# Controllerboard.net
KiCad netlist of a schematic drawn in EAGLE
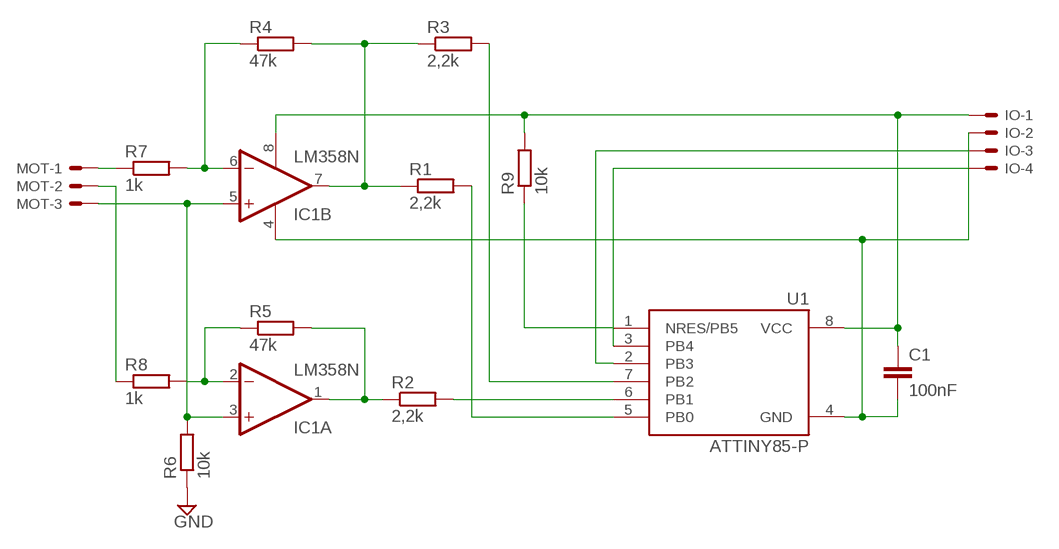
[diagram p0: schematic, sheet 1]

(export (version "E")
  (design (tool "Eeschema 10.0.6"))
  (components
    (comp (ref "C1")
      (value "100nF")
      (footprint "eagle-import:C025-024X044")
      (libsource (lib "eagle-import") (part "C-EU025-024X044"))
    )
    (comp (ref "IC1")
      (value "LM358N")
      (footprint "eagle-import:DIL08")
      (libsource (lib "eagle-import") (part "LM358N"))
    )
    (comp (ref "IO")
      (value "KK-156-4")
      (footprint "eagle-import:KK-156-4")
      (libsource (lib "eagle-import") (part "KK-156-4"))
    )
    (comp (ref "MOT")
      (value "KK-156-3")
      (footprint "eagle-import:KK-156-3")
      (libsource (lib "eagle-import") (part "KK-156-3"))
    )
    (comp (ref "R1")
      (value "2,2k")
      (footprint "eagle-import:0204_7")
      (libsource (lib "eagle-import") (part "resistor_R-EU_0204/7"))
    )
    (comp (ref "R2")
      (value "2,2k")
      (footprint "eagle-import:0204_7")
      (libsource (lib "eagle-import") (part "resistor_R-EU_0204/7"))
    )
    (comp (ref "R3")
      (value "2,2k")
      (footprint "eagle-import:0204_7")
      (libsource (lib "eagle-import") (part "resistor_R-EU_0204/7"))
    )
    (comp (ref "R4")
      (value "47k")
      (footprint "eagle-import:0204_7")
      (libsource (lib "eagle-import") (part "resistor_R-EU_0204/7"))
    )
    (comp (ref "R5")
      (value "47k")
      (footprint "eagle-import:0204_7")
      (libsource (lib "eagle-import") (part "resistor_R-EU_0204/7"))
    )
    (comp (ref "R6")
      (value "10k")
      (footprint "eagle-import:0204_7")
      (libsource (lib "eagle-import") (part "resistor_R-EU_0204/7"))
    )
    (comp (ref "R7")
      (value "1k")
      (footprint "eagle-import:0204_7")
      (libsource (lib "eagle-import") (part "resistor_R-EU_0204/7"))
    )
    (comp (ref "R8")
      (value "1k")
      (footprint "eagle-import:0204_7")
      (libsource (lib "eagle-import") (part "resistor_R-EU_0204/7"))
    )
    (comp (ref "R9")
      (value "10k")
      (footprint "eagle-import:0204_7")
      (libsource (lib "eagle-import") (part "R-EU_0204/7"))
    )
    (comp (ref "U1")
      (value "ATTINY85-P")
      (footprint "eagle-import:PDIP08_300MIL")
      (libsource (lib "eagle-import") (part "ATTINY85P-"))
    )
  )
  (nets
    (net (code "1") (name "GND") (class "Default")
      (node (ref "C1") (pin "2") (pinfunction "2_2") (pintype "passive"))
      (node (ref "IC1") (pin "4") (pinfunction "V-_4") (pintype "power_in"))
      (node (ref "IO") (pin "2") (pinfunction "S_2") (pintype "passive"))
      (node (ref "R6") (pin "1") (pinfunction "1_1") (pintype "passive"))
      (node (ref "U1") (pin "4") (pinfunction "GND_4") (pintype "power_in"))
    )
    (net (code "2") (name "Net-(IC1A-+IN)") (class "Default")
      (node (ref "IC1") (pin "3") (pinfunction "+IN_3") (pintype "input"))
      (node (ref "IC1") (pin "5") (pinfunction "+IN_5") (pintype "input"))
      (node (ref "MOT") (pin "3") (pinfunction "S_3") (pintype "passive"))
      (node (ref "R6") (pin "2") (pinfunction "2_2") (pintype "passive"))
    )
    (net (code "3") (name "Net-(IC1A--IN)") (class "Default")
      (node (ref "IC1") (pin "2") (pinfunction "-IN_2") (pintype "input"))
      (node (ref "R5") (pin "1") (pinfunction "1_1") (pintype "passive"))
      (node (ref "R8") (pin "2") (pinfunction "2_2") (pintype "passive"))
    )
    (net (code "4") (name "Net-(IC1A-OUT)") (class "Default")
      (node (ref "IC1") (pin "1") (pinfunction "OUT_1") (pintype "output"))
      (node (ref "R2") (pin "1") (pinfunction "1_1") (pintype "passive"))
      (node (ref "R5") (pin "2") (pinfunction "2_2") (pintype "passive"))
    )
    (net (code "5") (name "Net-(IC1B--IN)") (class "Default")
      (node (ref "IC1") (pin "6") (pinfunction "-IN_6") (pintype "input"))
      (node (ref "R4") (pin "1") (pinfunction "1_1") (pintype "passive"))
      (node (ref "R7") (pin "2") (pinfunction "2_2") (pintype "passive"))
    )
    (net (code "6") (name "Net-(IC1B-OUT)") (class "Default")
      (node (ref "IC1") (pin "7") (pinfunction "OUT_7") (pintype "output"))
      (node (ref "R1") (pin "1") (pinfunction "1_1") (pintype "passive"))
      (node (ref "R3") (pin "1") (pinfunction "1_1") (pintype "passive"))
      (node (ref "R4") (pin "2") (pinfunction "2_2") (pintype "passive"))
    )
    (net (code "7") (name "Net-(IC1C-V+)") (class "Default")
      (node (ref "C1") (pin "1") (pinfunction "1_1") (pintype "passive"))
      (node (ref "IC1") (pin "8") (pinfunction "V+_8") (pintype "power_in"))
      (node (ref "IO") (pin "1") (pinfunction "S_1") (pintype "passive"))
      (node (ref "R9") (pin "2") (pinfunction "2_2") (pintype "passive"))
      (node (ref "U1") (pin "8") (pinfunction "VCC_8") (pintype "power_in"))
    )
    (net (code "8") (name "Net-(IOC-S)") (class "Default")
      (node (ref "IO") (pin "3") (pinfunction "S_3") (pintype "passive"))
      (node (ref "U1") (pin "2") (pinfunction "PB3_2") (pintype "bidirectional"))
    )
    (net (code "9") (name "Net-(IOD-S)") (class "Default")
      (node (ref "IO") (pin "4") (pinfunction "S_4") (pintype "passive"))
      (node (ref "U1") (pin "3") (pinfunction "PB4_3") (pintype "bidirectional"))
    )
    (net (code "10") (name "Net-(MOTA-S)") (class "Default")
      (node (ref "MOT") (pin "1") (pinfunction "S_1") (pintype "passive"))
      (node (ref "R7") (pin "1") (pinfunction "1_1") (pintype "passive"))
    )
    (net (code "11") (name "Net-(MOTB-S)") (class "Default")
      (node (ref "MOT") (pin "2") (pinfunction "S_2") (pintype "passive"))
      (node (ref "R8") (pin "1") (pinfunction "1_1") (pintype "passive"))
    )
    (net (code "12") (name "Net-(U1-NRES{slash}PB5)") (class "Default")
      (node (ref "R9") (pin "1") (pinfunction "1_1") (pintype "passive"))
      (node (ref "U1") (pin "1") (pinfunction "NRES/PB5_1") (pintype "bidirectional"))
    )
    (net (code "13") (name "Net-(U1-PB0)") (class "Default")
      (node (ref "R1") (pin "2") (pinfunction "2_2") (pintype "passive"))
      (node (ref "U1") (pin "5") (pinfunction "PB0_5") (pintype "bidirectional"))
    )
    (net (code "14") (name "Net-(U1-PB1)") (class "Default")
      (node (ref "R2") (pin "2") (pinfunction "2_2") (pintype "passive"))
      (node (ref "U1") (pin "6") (pinfunction "PB1_6") (pintype "bidirectional"))
    )
    (net (code "15") (name "Net-(U1-PB2)") (class "Default")
      (node (ref "R3") (pin "2") (pinfunction "2_2") (pintype "passive"))
      (node (ref "U1") (pin "7") (pinfunction "PB2_7") (pintype "bidirectional"))
    )
  )
)
